# DAC.net
KiCad netlist of a schematic drawn in Altium Designer
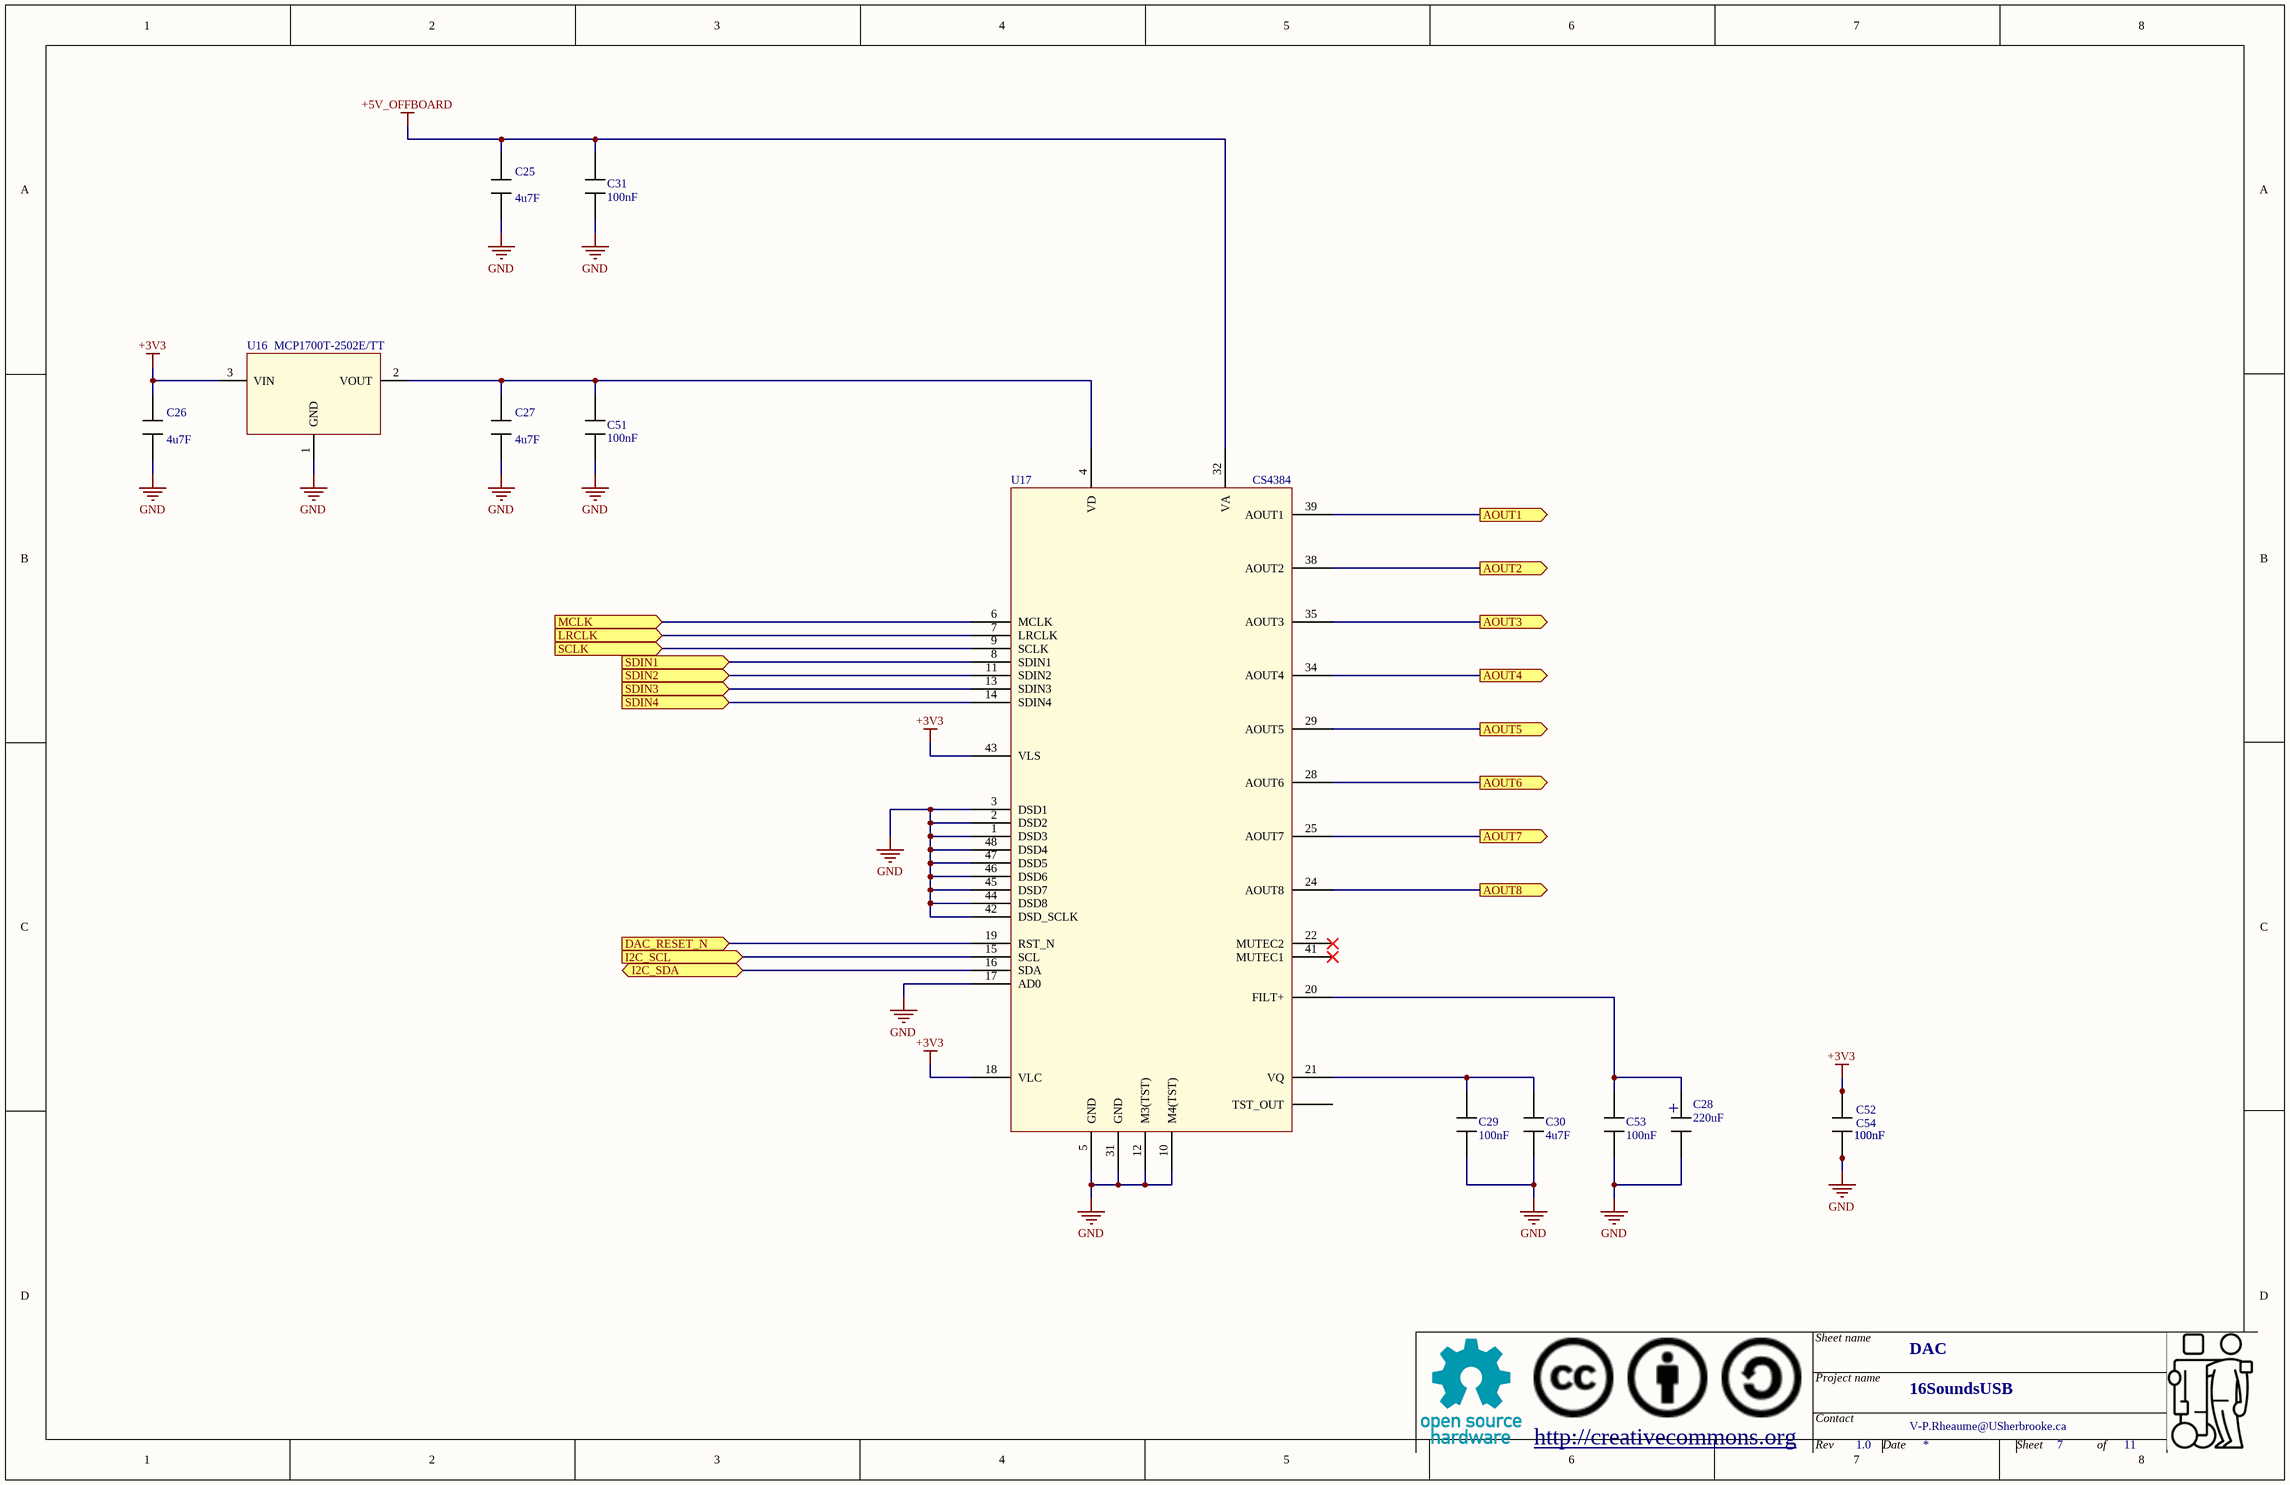
[diagram p0: DAC.SchDoc]

(export (version "E")
  (design (tool "Eeschema 10.0.6"))
  (components
    (comp (ref "C25")
      (value "4u7F")
      (footprint "0805")
      (description "Capacitor")
      (fields (field (name "MFG") "Samsung"))
      (libsource (lib "INTER_2014") (part "Capacitor"))
    )
    (comp (ref "C26")
      (value "4u7F")
      (footprint "0805")
      (description "Capacitor")
      (fields (field (name "MFG") "Samsung"))
      (libsource (lib "INTER_2014") (part "Capacitor"))
    )
    (comp (ref "C27")
      (value "4u7F")
      (footprint "0805")
      (description "Capacitor")
      (fields (field (name "MFG") "Samsung"))
      (libsource (lib "INTER_2014") (part "Capacitor"))
    )
    (comp (ref "C28")
      (value "220uF")
      (footprint "CAP_RAD_SMD_DIA315")
      (description "Capacitor")
      (fields (field (name "MFG") "Nichicon") (field (name "Comment") "Capacitor_Polarized"))
      (libsource (lib "INTER_2014") (part "Capacitor_Polarized"))
    )
    (comp (ref "C29")
      (value "100nF")
      (footprint "0603")
      (description "Capacitor")
      (fields (field (name "MFG") "Samsung"))
      (libsource (lib "INTER_2014") (part "Capacitor"))
    )
    (comp (ref "C30")
      (value "4u7F")
      (footprint "0805")
      (description "Capacitor")
      (fields (field (name "MFG") "Samsung"))
      (libsource (lib "INTER_2014") (part "Capacitor"))
    )
    (comp (ref "C31")
      (value "100nF")
      (footprint "0603")
      (description "Capacitor")
      (fields (field (name "MFG") "Samsung"))
      (libsource (lib "INTER_2014") (part "Capacitor"))
    )
    (comp (ref "C51")
      (value "100nF")
      (footprint "0603")
      (description "Capacitor")
      (fields (field (name "MFG") "Samsung"))
      (libsource (lib "INTER_2014") (part "Capacitor"))
    )
    (comp (ref "C52")
      (value "100nF")
      (footprint "0603")
      (description "Capacitor")
      (fields (field (name "MFG") "Samsung"))
      (libsource (lib "INTER_2014") (part "Capacitor"))
    )
    (comp (ref "C53")
      (value "100nF")
      (footprint "0603")
      (description "Capacitor")
      (fields (field (name "MFG") "Samsung"))
      (libsource (lib "INTER_2014") (part "Capacitor"))
    )
    (comp (ref "C54")
      (value "100nF")
      (footprint "0603")
      (description "Capacitor")
      (fields (field (name "MFG") "Samsung"))
      (libsource (lib "INTER_2014") (part "Capacitor"))
    )
    (comp (ref "U16")
      (value "MCP1700")
      (footprint "SOT23_132")
      (description "Linear voltage regulator")
      (fields (field (name "MFG") "Microchip") (field (name "MFG_PN") "MCP1700T-2502E/TT"))
      (libsource (lib "INTER_2014") (part "MCP1700"))
    )
    (comp (ref "U17")
      (value "CS4384")
      (footprint "LQFP_48L_CIRRUS")
      (description "DAC, 24-bit, 8 chan, 192kHz, PCM, TDM, DSD, LQFP48")
      (fields (field (name "MFG") "Cirrus"))
      (libsource (lib "INTER_2014") (part "CS4384"))
    )
  )
  (nets
    (net (code "1") (name "+3V3") (class "Default")
      (node (ref "C26") (pin "1") (pintype "passive"))
      (node (ref "C52") (pin "1") (pintype "passive"))
      (node (ref "C54") (pin "1") (pintype "passive"))
      (node (ref "U16") (pin "3") (pinfunction "VIN_3") (pintype "passive"))
      (node (ref "U17") (pin "18") (pinfunction "VLC_18") (pintype "passive"))
      (node (ref "U17") (pin "43") (pinfunction "VLS_43") (pintype "passive"))
    )
    (net (code "2") (name "+5V_OFFBOARD") (class "Default")
      (node (ref "C25") (pin "1") (pintype "passive"))
      (node (ref "C31") (pin "1") (pintype "passive"))
      (node (ref "U17") (pin "32") (pinfunction "VA_32") (pintype "passive"))
    )
    (net (code "3") (name "/AOUT1") (class "Default")
      (node (ref "U17") (pin "39") (pinfunction "AOUT1_39") (pintype "passive"))
    )
    (net (code "4") (name "/AOUT2") (class "Default")
      (node (ref "U17") (pin "38") (pinfunction "AOUT2_38") (pintype "passive"))
    )
    (net (code "5") (name "/AOUT3") (class "Default")
      (node (ref "U17") (pin "35") (pinfunction "AOUT3_35") (pintype "passive"))
    )
    (net (code "6") (name "/AOUT4") (class "Default")
      (node (ref "U17") (pin "34") (pinfunction "AOUT4_34") (pintype "passive"))
    )
    (net (code "7") (name "/AOUT5") (class "Default")
      (node (ref "U17") (pin "29") (pinfunction "AOUT5_29") (pintype "passive"))
    )
    (net (code "8") (name "/AOUT6") (class "Default")
      (node (ref "U17") (pin "28") (pinfunction "AOUT6_28") (pintype "passive"))
    )
    (net (code "9") (name "/AOUT7") (class "Default")
      (node (ref "U17") (pin "25") (pinfunction "AOUT7_25") (pintype "passive"))
    )
    (net (code "10") (name "/AOUT8") (class "Default")
      (node (ref "U17") (pin "24") (pinfunction "AOUT8_24") (pintype "passive"))
    )
    (net (code "11") (name "/DAC_RESET_N") (class "Default")
      (node (ref "U17") (pin "19") (pinfunction "RST_N_19") (pintype "passive"))
    )
    (net (code "12") (name "/I2C_SCL") (class "Default")
      (node (ref "U17") (pin "15") (pinfunction "SCL_15") (pintype "passive"))
    )
    (net (code "13") (name "/I2C_SDA") (class "Default")
      (node (ref "U17") (pin "16") (pinfunction "SDA_16") (pintype "passive"))
    )
    (net (code "14") (name "/LRCLK") (class "Default")
      (node (ref "U17") (pin "7") (pinfunction "LRCLK_7") (pintype "passive"))
    )
    (net (code "15") (name "/MCLK") (class "Default")
      (node (ref "U17") (pin "6") (pinfunction "MCLK_6") (pintype "passive"))
    )
    (net (code "16") (name "/SCLK") (class "Default")
      (node (ref "U17") (pin "9") (pinfunction "SCLK_9") (pintype "passive"))
    )
    (net (code "17") (name "/SDIN1") (class "Default")
      (node (ref "U17") (pin "8") (pinfunction "SDIN1_8") (pintype "passive"))
    )
    (net (code "18") (name "/SDIN2") (class "Default")
      (node (ref "U17") (pin "11") (pinfunction "SDIN2_11") (pintype "passive"))
    )
    (net (code "19") (name "/SDIN3") (class "Default")
      (node (ref "U17") (pin "13") (pinfunction "SDIN3_13") (pintype "passive"))
    )
    (net (code "20") (name "/SDIN4") (class "Default")
      (node (ref "U17") (pin "14") (pinfunction "SDIN4_14") (pintype "passive"))
    )
    (net (code "21") (name "GND") (class "Default")
      (node (ref "C25") (pin "2") (pintype "passive"))
      (node (ref "C26") (pin "2") (pintype "passive"))
      (node (ref "C27") (pin "2") (pintype "passive"))
      (node (ref "C28") (pin "-") (pintype "passive"))
      (node (ref "C29") (pin "2") (pintype "passive"))
      (node (ref "C30") (pin "2") (pintype "passive"))
      (node (ref "C31") (pin "2") (pintype "passive"))
      (node (ref "C51") (pin "2") (pintype "passive"))
      (node (ref "C52") (pin "2") (pintype "passive"))
      (node (ref "C53") (pin "2") (pintype "passive"))
      (node (ref "C54") (pin "2") (pintype "passive"))
      (node (ref "U16") (pin "1") (pinfunction "GND_1") (pintype "passive"))
      (node (ref "U17") (pin "1") (pinfunction "DSD3_1") (pintype "passive"))
      (node (ref "U17") (pin "10") (pinfunction "M4(TST)_10") (pintype "passive"))
      (node (ref "U17") (pin "12") (pinfunction "M3(TST)_12") (pintype "passive"))
      (node (ref "U17") (pin "17") (pinfunction "AD0_17") (pintype "passive"))
      (node (ref "U17") (pin "2") (pinfunction "DSD2_2") (pintype "passive"))
      (node (ref "U17") (pin "3") (pinfunction "DSD1_3") (pintype "passive"))
      (node (ref "U17") (pin "31") (pinfunction "GND_31") (pintype "passive"))
      (node (ref "U17") (pin "42") (pinfunction "DSD_SCLK_42") (pintype "passive"))
      (node (ref "U17") (pin "44") (pinfunction "DSD8_44") (pintype "passive"))
      (node (ref "U17") (pin "45") (pinfunction "DSD7_45") (pintype "passive"))
      (node (ref "U17") (pin "46") (pinfunction "DSD6_46") (pintype "passive"))
      (node (ref "U17") (pin "47") (pinfunction "DSD5_47") (pintype "passive"))
      (node (ref "U17") (pin "48") (pinfunction "DSD4_48") (pintype "passive"))
      (node (ref "U17") (pin "5") (pinfunction "GND_5") (pintype "passive"))
    )
    (net (code "22") (name "Net-(U16-VOUT)") (class "Default")
      (node (ref "C27") (pin "1") (pintype "passive"))
      (node (ref "C51") (pin "1") (pintype "passive"))
      (node (ref "U16") (pin "2") (pinfunction "VOUT_2") (pintype "passive"))
      (node (ref "U17") (pin "4") (pinfunction "VD_4") (pintype "passive"))
    )
    (net (code "23") (name "Net-(U17-FILT+)") (class "Default")
      (node (ref "C28") (pin "+") (pintype "passive"))
      (node (ref "C53") (pin "1") (pintype "passive"))
      (node (ref "U17") (pin "20") (pinfunction "FILT+_20") (pintype "passive"))
    )
    (net (code "24") (name "Net-(U17-VQ)") (class "Default")
      (node (ref "C29") (pin "1") (pintype "passive"))
      (node (ref "C30") (pin "1") (pintype "passive"))
      (node (ref "U17") (pin "21") (pinfunction "VQ_21") (pintype "passive"))
    )
    (net (code "25") (name "unconnected-(U17-MUTEC1-Pad41)") (class "Default")
      (node (ref "U17") (pin "41") (pinfunction "MUTEC1_41") (pintype "passive+no_connect"))
    )
    (net (code "26") (name "unconnected-(U17-MUTEC2-Pad22)") (class "Default")
      (node (ref "U17") (pin "22") (pinfunction "MUTEC2_22") (pintype "passive+no_connect"))
    )
    (net (code "27") (name "unconnected-(U17-TST_OUT-Pad23)") (class "Default")
      (node (ref "U17") (pin "23") (pinfunction "TST_OUT_23") (pintype "passive"))
    )
    (net (code "28") (name "unconnected-(U17-TST_OUT-Pad26)") (class "Default")
      (node (ref "U17") (pin "26") (pinfunction "TST_OUT_26") (pintype "passive"))
    )
    (net (code "29") (name "unconnected-(U17-TST_OUT-Pad27)") (class "Default")
      (node (ref "U17") (pin "27") (pinfunction "TST_OUT_27") (pintype "passive"))
    )
    (net (code "30") (name "unconnected-(U17-TST_OUT-Pad30)") (class "Default")
      (node (ref "U17") (pin "30") (pinfunction "TST_OUT_30") (pintype "passive"))
    )
    (net (code "31") (name "unconnected-(U17-TST_OUT-Pad33)") (class "Default")
      (node (ref "U17") (pin "33") (pinfunction "TST_OUT_33") (pintype "passive"))
    )
    (net (code "32") (name "unconnected-(U17-TST_OUT-Pad36)") (class "Default")
      (node (ref "U17") (pin "36") (pinfunction "TST_OUT_36") (pintype "passive"))
    )
    (net (code "33") (name "unconnected-(U17-TST_OUT-Pad37)") (class "Default")
      (node (ref "U17") (pin "37") (pinfunction "TST_OUT_37") (pintype "passive"))
    )
    (net (code "34") (name "unconnected-(U17-TST_OUT-Pad40)") (class "Default")
      (node (ref "U17") (pin "40") (pinfunction "TST_OUT_40") (pintype "passive"))
    )
  )
)
